# Transmitter_V1.net
KiCad netlist of a schematic drawn in EAGLE
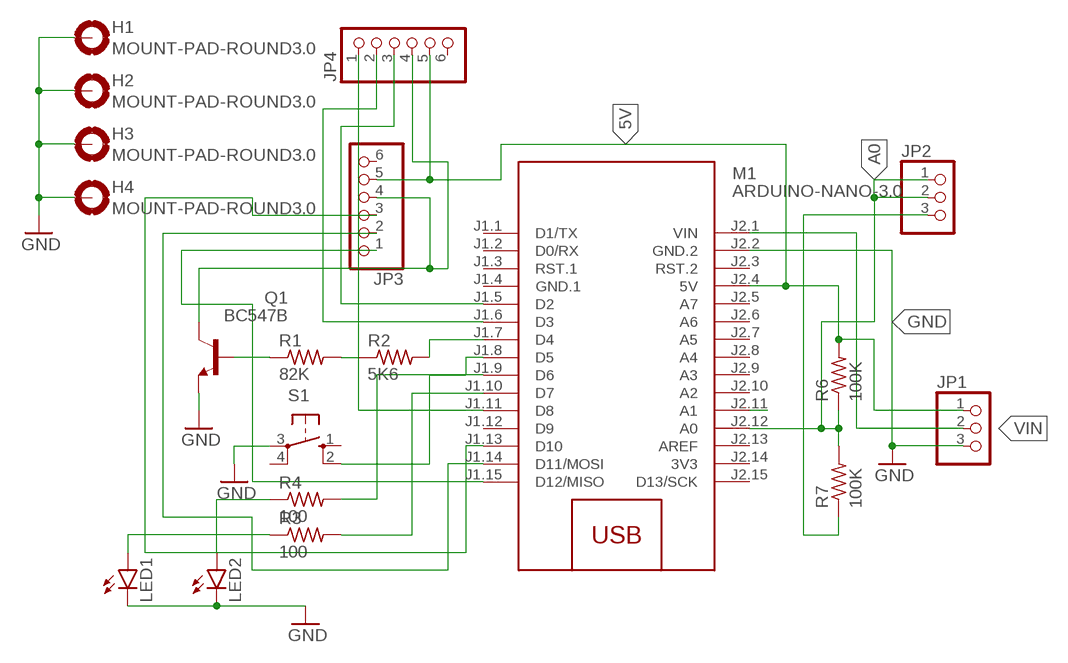
[diagram p0: schematic, sheet 1]

(export (version "E")
  (design (tool "Eeschema 10.0.6"))
  (components
    (comp (ref "H1")
      (value "MOUNT-PAD-ROUND3.0")
      (footprint "eagle-import:3,0-PAD")
      (libsource (lib "eagle-import") (part "MOUNT-PAD-ROUND3.0"))
    )
    (comp (ref "H2")
      (value "MOUNT-PAD-ROUND3.0")
      (footprint "eagle-import:3,0-PAD")
      (libsource (lib "eagle-import") (part "MOUNT-PAD-ROUND3.0"))
    )
    (comp (ref "H3")
      (value "MOUNT-PAD-ROUND3.0")
      (footprint "eagle-import:3,0-PAD")
      (libsource (lib "eagle-import") (part "MOUNT-PAD-ROUND3.0"))
    )
    (comp (ref "H4")
      (value "MOUNT-PAD-ROUND3.0")
      (footprint "eagle-import:3,0-PAD")
      (libsource (lib "eagle-import") (part "MOUNT-PAD-ROUND3.0"))
    )
    (comp (ref "JP1")
      (value "PINHD-1X3")
      (footprint "eagle-import:1X03")
      (libsource (lib "eagle-import") (part "PINHD-1X3"))
    )
    (comp (ref "JP2")
      (value "PINHD-1X3")
      (footprint "eagle-import:1X03")
      (libsource (lib "eagle-import") (part "PINHD-1X3"))
    )
    (comp (ref "JP3")
      (value "PINHD-1X6")
      (footprint "eagle-import:1X06")
      (libsource (lib "eagle-import") (part "PINHD-1X6"))
    )
    (comp (ref "JP4")
      (value "PINHD-1X6")
      (footprint "eagle-import:1X06")
      (libsource (lib "eagle-import") (part "PINHD-1X6"))
    )
    (comp (ref "LED1")
      (value "LED3MM")
      (footprint "eagle-import:LED3MM")
      (libsource (lib "eagle-import") (part "LED3MM"))
    )
    (comp (ref "LED2")
      (value "LED3MM")
      (footprint "eagle-import:LED3MM")
      (libsource (lib "eagle-import") (part "LED3MM"))
    )
    (comp (ref "M1")
      (value "ARDUINO-NANO-3.0")
      (footprint "eagle-import:ARDUINO-NANO-3.0")
      (libsource (lib "eagle-import") (part "ARDUINO-NANO-3.0"))
    )
    (comp (ref "Q1")
      (value "BC547B")
      (footprint "eagle-import:TO92")
      (libsource (lib "eagle-import") (part "BC547B"))
    )
    (comp (ref "R1")
      (value "82K")
      (footprint "eagle-import:0207_7")
      (libsource (lib "eagle-import") (part "R-US_0207/7"))
    )
    (comp (ref "R2")
      (value "5K6")
      (footprint "eagle-import:0207_7")
      (libsource (lib "eagle-import") (part "R-US_0207/7"))
    )
    (comp (ref "R3")
      (value "100")
      (footprint "eagle-import:0207_7")
      (libsource (lib "eagle-import") (part "R-US_0207/7"))
    )
    (comp (ref "R4")
      (value "100")
      (footprint "eagle-import:0207_7")
      (libsource (lib "eagle-import") (part "R-US_0207/7"))
    )
    (comp (ref "R6")
      (value "100K")
      (footprint "eagle-import:0207_7")
      (libsource (lib "eagle-import") (part "R-US_0207/7"))
    )
    (comp (ref "R7")
      (value "100K")
      (footprint "eagle-import:0207_7")
      (libsource (lib "eagle-import") (part "R-US_0207/7"))
    )
    (comp (ref "S1")
      (value "10-XX")
      (footprint "eagle-import:B3F-10XX")
      (fields (field (name "MPN") "B3F-1000"))
      (libsource (lib "eagle-import") (part "10-XX"))
    )
  )
  (nets
    (net (code "1") (name "/3V3") (class "Default")
      (node (ref "M1") (pin "J2.14") (pinfunction "3V3_J2.14") (pintype "power_in"))
    )
    (net (code "2") (name "/GND.1") (class "Default")
      (node (ref "M1") (pin "J1.4") (pinfunction "GND.1_J1.4") (pintype "power_in"))
    )
    (net (code "3") (name "5V") (class "Default")
      (node (ref "JP1") (pin "1") (pinfunction "1_1") (pintype "passive"))
      (node (ref "JP3") (pin "5") (pinfunction "5_5") (pintype "passive"))
      (node (ref "JP4") (pin "5") (pinfunction "5_5") (pintype "passive"))
      (node (ref "M1") (pin "J2.4") (pinfunction "5V_J2.4") (pintype "power_in"))
      (node (ref "R6") (pin "2") (pinfunction "2_2") (pintype "passive"))
    )
    (net (code "4") (name "A0") (class "Default")
      (node (ref "JP2") (pin "1") (pinfunction "1_1") (pintype "passive"))
      (node (ref "JP2") (pin "2") (pinfunction "2_2") (pintype "passive"))
      (node (ref "M1") (pin "J2.12") (pinfunction "A0_J2.12") (pintype "bidirectional"))
      (node (ref "R6") (pin "1") (pinfunction "1_1") (pintype "passive"))
      (node (ref "R7") (pin "2") (pinfunction "2_2") (pintype "passive"))
    )
    (net (code "5") (name "GND") (class "Default")
      (node (ref "H1") (pin "B3,0") (pinfunction "MOUNT_B3,0") (pintype "passive"))
      (node (ref "H2") (pin "B3,0") (pinfunction "MOUNT_B3,0") (pintype "passive"))
      (node (ref "H3") (pin "B3,0") (pinfunction "MOUNT_B3,0") (pintype "passive"))
      (node (ref "H4") (pin "B3,0") (pinfunction "MOUNT_B3,0") (pintype "passive"))
      (node (ref "JP1") (pin "3") (pinfunction "3_3") (pintype "passive"))
      (node (ref "LED1") (pin "K") (pinfunction "C_K") (pintype "passive"))
      (node (ref "LED2") (pin "K") (pinfunction "C_K") (pintype "passive"))
      (node (ref "M1") (pin "J2.2") (pinfunction "GND.2_J2.2") (pintype "power_in"))
      (node (ref "Q1") (pin "1") (pinfunction "E_1") (pintype "passive"))
      (node (ref "S1") (pin "3") (pinfunction "P_3") (pintype "passive"))
    )
    (net (code "6") (name "Net-(JP2-Pad3)") (class "Default")
      (node (ref "JP2") (pin "3") (pinfunction "3_3") (pintype "passive"))
      (node (ref "R7") (pin "1") (pinfunction "1_1") (pintype "passive"))
    )
    (net (code "7") (name "Net-(LED1-PadA)") (class "Default")
      (node (ref "LED1") (pin "A") (pinfunction "A_A") (pintype "passive"))
      (node (ref "R3") (pin "1") (pinfunction "1_1") (pintype "passive"))
    )
    (net (code "8") (name "Net-(LED2-PadA)") (class "Default")
      (node (ref "LED2") (pin "A") (pinfunction "A_A") (pintype "passive"))
      (node (ref "R4") (pin "1") (pinfunction "1_1") (pintype "passive"))
    )
    (net (code "9") (name "Net-(M1-D2)") (class "Default")
      (node (ref "JP4") (pin "3") (pinfunction "3_3") (pintype "passive"))
      (node (ref "M1") (pin "J1.5") (pinfunction "D2_J1.5") (pintype "bidirectional"))
    )
    (net (code "10") (name "Net-(M1-D3)") (class "Default")
      (node (ref "JP4") (pin "2") (pinfunction "2_2") (pintype "passive"))
      (node (ref "M1") (pin "J1.6") (pinfunction "D3_J1.6") (pintype "bidirectional"))
    )
    (net (code "11") (name "Net-(M1-D4)") (class "Default")
      (node (ref "M1") (pin "J1.7") (pinfunction "D4_J1.7") (pintype "bidirectional"))
      (node (ref "R2") (pin "2") (pinfunction "2_2") (pintype "passive"))
    )
    (net (code "12") (name "Net-(M1-D5)") (class "Default")
      (node (ref "M1") (pin "J1.8") (pinfunction "D5_J1.8") (pintype "bidirectional"))
      (node (ref "S1") (pin "2") (pinfunction "S1_2") (pintype "passive"))
    )
    (net (code "13") (name "Net-(M1-D6)") (class "Default")
      (node (ref "M1") (pin "J1.9") (pinfunction "D6_J1.9") (pintype "bidirectional"))
      (node (ref "R4") (pin "2") (pinfunction "2_2") (pintype "passive"))
    )
    (net (code "14") (name "Net-(M1-D7)") (class "Default")
      (node (ref "M1") (pin "J1.10") (pinfunction "D7_J1.10") (pintype "bidirectional"))
      (node (ref "R3") (pin "2") (pinfunction "2_2") (pintype "passive"))
    )
    (net (code "15") (name "Net-(M1-D8)") (class "Default")
      (node (ref "JP4") (pin "1") (pinfunction "1_1") (pintype "passive"))
      (node (ref "M1") (pin "J1.11") (pinfunction "D8_J1.11") (pintype "bidirectional"))
    )
    (net (code "16") (name "Net-(M1-D10)") (class "Default")
      (node (ref "JP3") (pin "3") (pinfunction "3_3") (pintype "passive"))
      (node (ref "M1") (pin "J1.13") (pinfunction "D10_J1.13") (pintype "bidirectional"))
    )
    (net (code "17") (name "Net-(M1-D11{slash}MOSI)") (class "Default")
      (node (ref "JP3") (pin "2") (pinfunction "2_2") (pintype "passive"))
      (node (ref "M1") (pin "J1.14") (pinfunction "D11/MOSI_J1.14") (pintype "bidirectional"))
    )
    (net (code "18") (name "Net-(M1-D12{slash}MISO)") (class "Default")
      (node (ref "JP3") (pin "1") (pinfunction "1_1") (pintype "passive"))
      (node (ref "M1") (pin "J1.15") (pinfunction "D12/MISO_J1.15") (pintype "bidirectional"))
    )
    (net (code "19") (name "Net-(Q1-B)") (class "Default")
      (node (ref "Q1") (pin "2") (pinfunction "B_2") (pintype "passive"))
      (node (ref "R1") (pin "1") (pinfunction "1_1") (pintype "passive"))
    )
    (net (code "20") (name "Net-(Q1-C)") (class "Default")
      (node (ref "JP3") (pin "4") (pinfunction "4_4") (pintype "passive"))
      (node (ref "JP4") (pin "4") (pinfunction "4_4") (pintype "passive"))
      (node (ref "Q1") (pin "3") (pinfunction "C_3") (pintype "passive"))
    )
    (net (code "21") (name "Net-(R1-Pad2)") (class "Default")
      (node (ref "R1") (pin "2") (pinfunction "2_2") (pintype "passive"))
      (node (ref "R2") (pin "1") (pinfunction "1_1") (pintype "passive"))
    )
    (net (code "22") (name "VIN") (class "Default")
      (node (ref "JP1") (pin "2") (pinfunction "2_2") (pintype "passive"))
      (node (ref "M1") (pin "J2.1") (pinfunction "VIN_J2.1") (pintype "power_in"))
    )
    (net (code "23") (name "unconnected-(JP3-Pad6)") (class "Default")
      (node (ref "JP3") (pin "6") (pinfunction "6_6") (pintype "passive"))
    )
    (net (code "24") (name "unconnected-(JP4-Pad6)") (class "Default")
      (node (ref "JP4") (pin "6") (pinfunction "6_6") (pintype "passive"))
    )
    (net (code "25") (name "unconnected-(M1-A1-PadJ2.11)") (class "Default")
      (node (ref "M1") (pin "J2.11") (pinfunction "A1_J2.11") (pintype "bidirectional"))
    )
    (net (code "26") (name "unconnected-(M1-A2-PadJ2.10)") (class "Default")
      (node (ref "M1") (pin "J2.10") (pinfunction "A2_J2.10") (pintype "bidirectional"))
    )
    (net (code "27") (name "unconnected-(M1-A3-PadJ2.9)") (class "Default")
      (node (ref "M1") (pin "J2.9") (pinfunction "A3_J2.9") (pintype "bidirectional"))
    )
    (net (code "28") (name "unconnected-(M1-A4-PadJ2.8)") (class "Default")
      (node (ref "M1") (pin "J2.8") (pinfunction "A4_J2.8") (pintype "bidirectional"))
    )
    (net (code "29") (name "unconnected-(M1-A5-PadJ2.7)") (class "Default")
      (node (ref "M1") (pin "J2.7") (pinfunction "A5_J2.7") (pintype "bidirectional"))
    )
    (net (code "30") (name "unconnected-(M1-A6-PadJ2.6)") (class "Default")
      (node (ref "M1") (pin "J2.6") (pinfunction "A6_J2.6") (pintype "bidirectional"))
    )
    (net (code "31") (name "unconnected-(M1-A7-PadJ2.5)") (class "Default")
      (node (ref "M1") (pin "J2.5") (pinfunction "A7_J2.5") (pintype "bidirectional"))
    )
    (net (code "32") (name "unconnected-(M1-AREF-PadJ2.13)") (class "Default")
      (node (ref "M1") (pin "J2.13") (pinfunction "AREF_J2.13") (pintype "bidirectional"))
    )
    (net (code "33") (name "unconnected-(M1-D0{slash}RX-PadJ1.2)") (class "Default")
      (node (ref "M1") (pin "J1.2") (pinfunction "D0/RX_J1.2") (pintype "bidirectional"))
    )
    (net (code "34") (name "unconnected-(M1-D1{slash}TX-PadJ1.1)") (class "Default")
      (node (ref "M1") (pin "J1.1") (pinfunction "D1/TX_J1.1") (pintype "bidirectional"))
    )
    (net (code "35") (name "unconnected-(M1-D9-PadJ1.12)") (class "Default")
      (node (ref "M1") (pin "J1.12") (pinfunction "D9_J1.12") (pintype "bidirectional"))
    )
    (net (code "36") (name "unconnected-(M1-D13{slash}SCK-PadJ2.15)") (class "Default")
      (node (ref "M1") (pin "J2.15") (pinfunction "D13/SCK_J2.15") (pintype "bidirectional"))
    )
    (net (code "37") (name "unconnected-(M1-RST.1-PadJ1.3)") (class "Default")
      (node (ref "M1") (pin "J1.3") (pinfunction "RST.1_J1.3") (pintype "bidirectional"))
    )
    (net (code "38") (name "unconnected-(M1-RST.2-PadJ2.3)") (class "Default")
      (node (ref "M1") (pin "J2.3") (pinfunction "RST.2_J2.3") (pintype "bidirectional"))
    )
    (net (code "39") (name "unconnected-(S1-P1-Pad4)") (class "Default")
      (node (ref "S1") (pin "4") (pinfunction "P1_4") (pintype "passive"))
    )
    (net (code "40") (name "unconnected-(S1-S-Pad1)") (class "Default")
      (node (ref "S1") (pin "1") (pinfunction "S_1") (pintype "passive"))
    )
  )
)
